# CON_RS232DCE_DB9F.net
KiCad netlist of a schematic drawn in Altium Designer
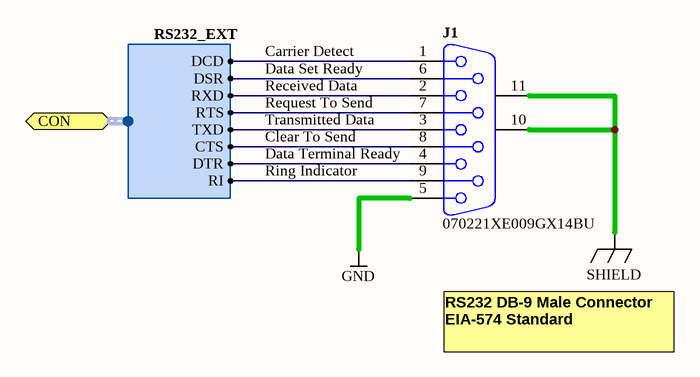
[diagram p0: CON_RS232DCE_DB9F.SchDoc]

(export (version "E")
  (design (tool "Eeschema 10.0.6"))
  (components
    (comp (ref "J1")
      (value "070221XE009GX14BU")
      (footprint "070221XE009GX14BU")
      (description "Connector DB9 SMD Male/Pins; SUYIN")
      (libsource (lib "AltiumDesignLibrary") (part "CON-DB-9-M-RA"))
    )
  )
  (nets
    (net (code "2") (name "/CTS") (class "Default")
      (node (ref "J1") (pin "8") (pinfunction "8_8") (pintype "passive"))
    )
    (net (code "3") (name "/DCD") (class "Default")
      (node (ref "J1") (pin "1") (pinfunction "1_1") (pintype "passive"))
    )
    (net (code "4") (name "/DSR") (class "Default")
      (node (ref "J1") (pin "6") (pinfunction "6_6") (pintype "passive"))
    )
    (net (code "5") (name "/DTR") (class "Default")
      (node (ref "J1") (pin "4") (pinfunction "4_4") (pintype "passive"))
    )
    (net (code "6") (name "/RI") (class "Default")
      (node (ref "J1") (pin "9") (pinfunction "9_9") (pintype "passive"))
    )
    (net (code "7") (name "/RTS") (class "Default")
      (node (ref "J1") (pin "7") (pinfunction "7_7") (pintype "passive"))
    )
    (net (code "8") (name "/RXD") (class "Default")
      (node (ref "J1") (pin "2") (pinfunction "2_2") (pintype "passive"))
    )
    (net (code "9") (name "/TXD") (class "Default")
      (node (ref "J1") (pin "3") (pinfunction "3_3") (pintype "passive"))
    )
    (net (code "11") (name "GND") (class "Default")
      (node (ref "J1") (pin "5") (pinfunction "5_5") (pintype "passive"))
    )
    (net (code "12") (name "SHIELD") (class "Default")
      (node (ref "J1") (pin "10") (pinfunction "MH1_10") (pintype "passive"))
      (node (ref "J1") (pin "11") (pinfunction "MH2_11") (pintype "passive"))
    )
  )
)
